# ghost.net
KiCad netlist of a schematic drawn in EAGLE
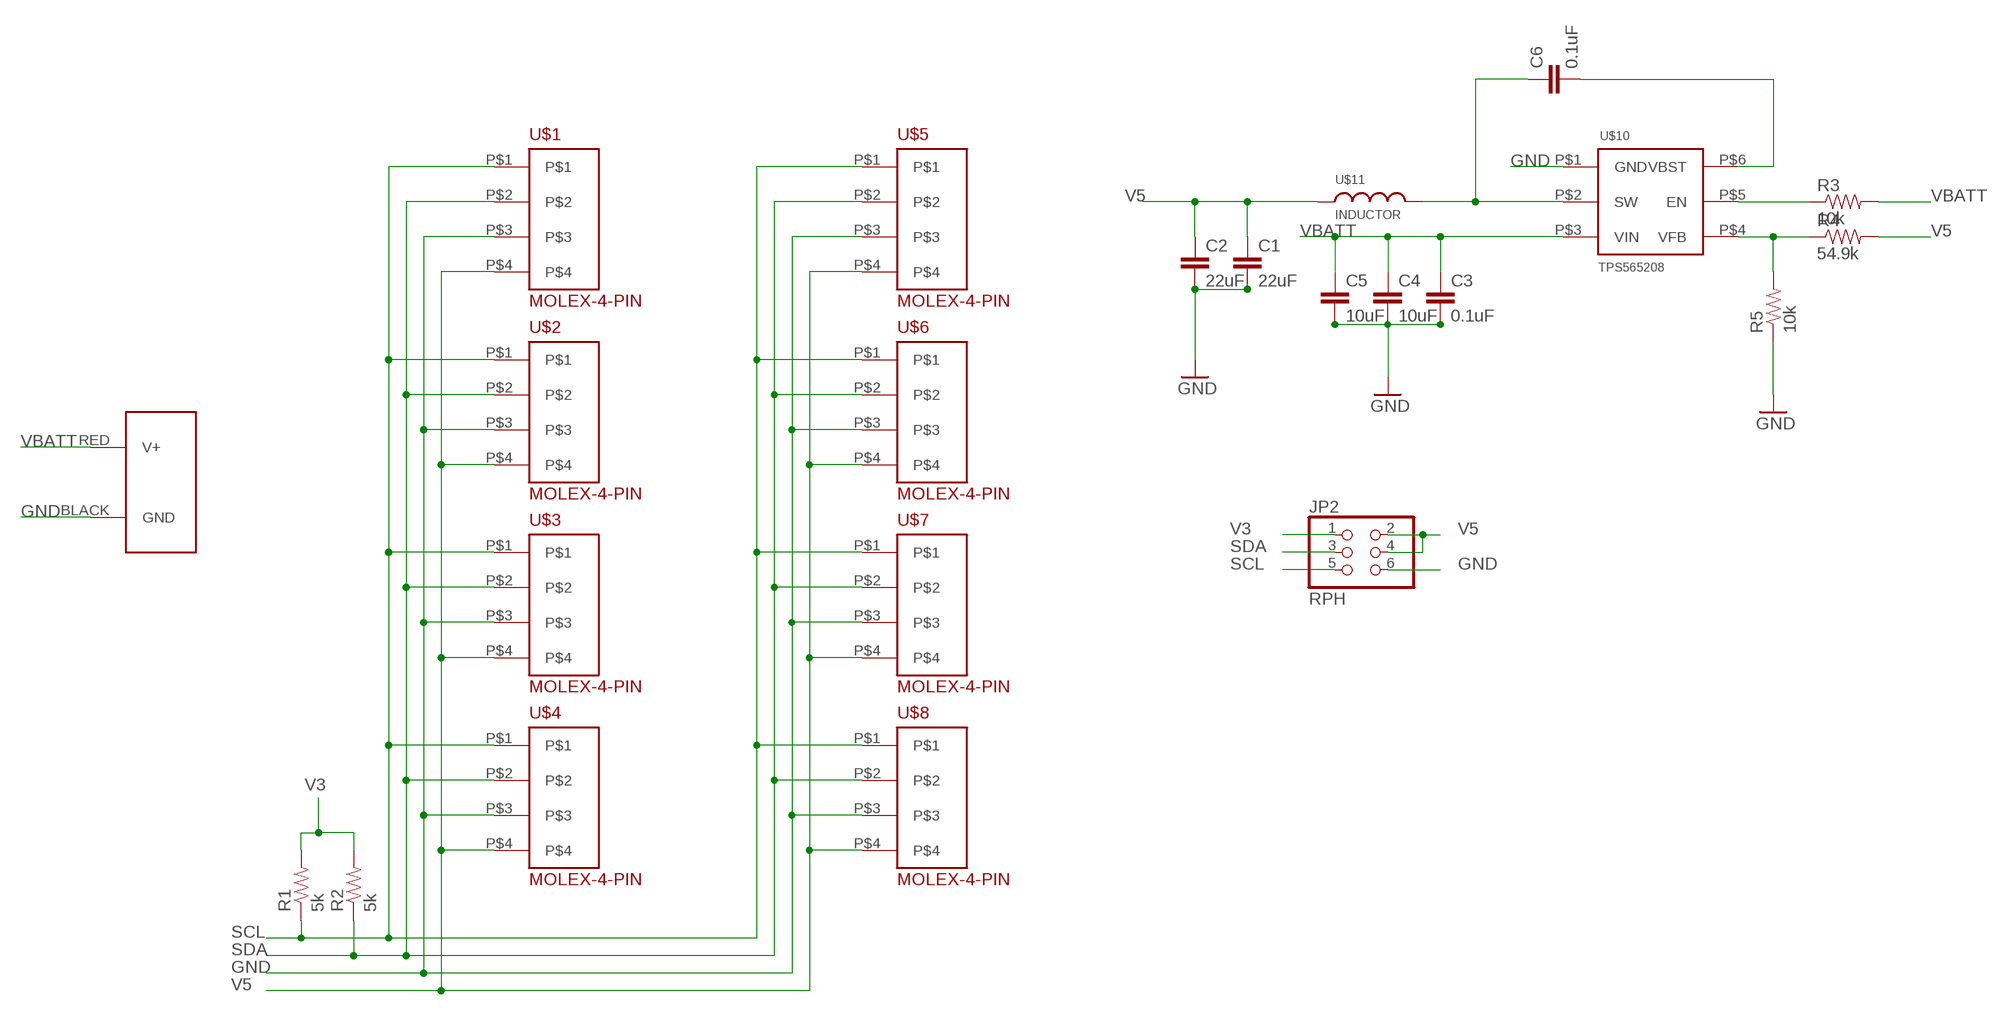
[diagram p0: schematic, sheet 1]

(export (version "E")
  (design (tool "Eeschema 10.0.6"))
  (components
    (comp (ref "C1")
      (value "22uF")
      (footprint "eagle-import:0805")
      (libsource (lib "eagle-import") (part "CAP0805"))
    )
    (comp (ref "C2")
      (value "22uF")
      (footprint "eagle-import:0805")
      (libsource (lib "eagle-import") (part "CAP0805"))
    )
    (comp (ref "C3")
      (value "0.1uF")
      (footprint "eagle-import:0805")
      (libsource (lib "eagle-import") (part "CAP0805"))
    )
    (comp (ref "C4")
      (value "10uF")
      (footprint "eagle-import:0805")
      (libsource (lib "eagle-import") (part "CAP0805"))
    )
    (comp (ref "C5")
      (value "10uF")
      (footprint "eagle-import:0805")
      (libsource (lib "eagle-import") (part "CAP0805"))
    )
    (comp (ref "C6")
      (value "0.1uF")
      (footprint "eagle-import:0805")
      (libsource (lib "eagle-import") (part "CAP0805"))
    )
    (comp (ref "J1")
      (value "POWERPOLE_POWER45A_HORIZONTAL_DRILL")
      (footprint "eagle-import:POWERPOLE_PAIR_45A_HORIZ_HOLE")
      (libsource (lib "eagle-import") (part "POWERPOLE_POWER45A_HORIZONTAL_DRILL"))
    )
    (comp (ref "JP2")
      (value "RPH")
      (footprint "eagle-import:2X03")
      (libsource (lib "eagle-import") (part "PINHD-2X3/OCT"))
    )
    (comp (ref "R1")
      (value "5k")
      (footprint "eagle-import:0805")
      (libsource (lib "eagle-import") (part "RESISTOR"))
    )
    (comp (ref "R2")
      (value "5k")
      (footprint "eagle-import:0805")
      (libsource (lib "eagle-import") (part "RESISTOR"))
    )
    (comp (ref "R3")
      (value "10k")
      (footprint "eagle-import:0805")
      (libsource (lib "eagle-import") (part "RESISTOR"))
    )
    (comp (ref "R4")
      (value "54.9k")
      (footprint "eagle-import:0805")
      (libsource (lib "eagle-import") (part "RESISTOR"))
    )
    (comp (ref "R5")
      (value "10k")
      (footprint "eagle-import:0805")
      (libsource (lib "eagle-import") (part "RESISTOR"))
    )
    (comp (ref "U$1")
      (value "MOLEX-4-PIN")
      (footprint "eagle-import:MOLEX-4-PIN")
      (libsource (lib "eagle-import") (part "MOLEX-4-PIN"))
    )
    (comp (ref "U$2")
      (value "MOLEX-4-PIN")
      (footprint "eagle-import:MOLEX-4-PIN")
      (libsource (lib "eagle-import") (part "MOLEX-4-PIN"))
    )
    (comp (ref "U$3")
      (value "MOLEX-4-PIN")
      (footprint "eagle-import:MOLEX-4-PIN")
      (libsource (lib "eagle-import") (part "MOLEX-4-PIN"))
    )
    (comp (ref "U$4")
      (value "MOLEX-4-PIN")
      (footprint "eagle-import:MOLEX-4-PIN")
      (libsource (lib "eagle-import") (part "MOLEX-4-PIN"))
    )
    (comp (ref "U$5")
      (value "MOLEX-4-PIN")
      (footprint "eagle-import:MOLEX-4-PIN")
      (libsource (lib "eagle-import") (part "MOLEX-4-PIN"))
    )
    (comp (ref "U$6")
      (value "MOLEX-4-PIN")
      (footprint "eagle-import:MOLEX-4-PIN")
      (libsource (lib "eagle-import") (part "MOLEX-4-PIN"))
    )
    (comp (ref "U$7")
      (value "MOLEX-4-PIN")
      (footprint "eagle-import:MOLEX-4-PIN")
      (libsource (lib "eagle-import") (part "MOLEX-4-PIN"))
    )
    (comp (ref "U$8")
      (value "MOLEX-4-PIN")
      (footprint "eagle-import:MOLEX-4-PIN")
      (libsource (lib "eagle-import") (part "MOLEX-4-PIN"))
    )
    (comp (ref "U$10")
      (value "TPS565208")
      (footprint "eagle-import:SOT-23-THIN-6")
      (libsource (lib "eagle-import") (part "TPS565208"))
    )
    (comp (ref "U$11")
      (value "INDUCTOR")
      (footprint "eagle-import:0805")
      (libsource (lib "eagle-import") (part "INDUCTOR"))
    )
  )
  (nets
    (net (code "1") (name "/SCL") (class "Default")
      (node (ref "JP2") (pin "5") (pinfunction "5_5") (pintype "passive"))
      (node (ref "R1") (pin "1") (pinfunction "1_1") (pintype "passive"))
      (node (ref "U$1") (pin "P$1") (pinfunction "P$1_P$1") (pintype "bidirectional"))
      (node (ref "U$2") (pin "P$1") (pinfunction "P$1_P$1") (pintype "bidirectional"))
      (node (ref "U$3") (pin "P$1") (pinfunction "P$1_P$1") (pintype "bidirectional"))
      (node (ref "U$4") (pin "P$1") (pinfunction "P$1_P$1") (pintype "bidirectional"))
      (node (ref "U$5") (pin "P$1") (pinfunction "P$1_P$1") (pintype "bidirectional"))
      (node (ref "U$6") (pin "P$1") (pinfunction "P$1_P$1") (pintype "bidirectional"))
      (node (ref "U$7") (pin "P$1") (pinfunction "P$1_P$1") (pintype "bidirectional"))
      (node (ref "U$8") (pin "P$1") (pinfunction "P$1_P$1") (pintype "bidirectional"))
    )
    (net (code "2") (name "/SDA") (class "Default")
      (node (ref "JP2") (pin "3") (pinfunction "3_3") (pintype "passive"))
      (node (ref "R2") (pin "1") (pinfunction "1_1") (pintype "passive"))
      (node (ref "U$1") (pin "P$2") (pinfunction "P$2_P$2") (pintype "bidirectional"))
      (node (ref "U$2") (pin "P$2") (pinfunction "P$2_P$2") (pintype "bidirectional"))
      (node (ref "U$3") (pin "P$2") (pinfunction "P$2_P$2") (pintype "bidirectional"))
      (node (ref "U$4") (pin "P$2") (pinfunction "P$2_P$2") (pintype "bidirectional"))
      (node (ref "U$5") (pin "P$2") (pinfunction "P$2_P$2") (pintype "bidirectional"))
      (node (ref "U$6") (pin "P$2") (pinfunction "P$2_P$2") (pintype "bidirectional"))
      (node (ref "U$7") (pin "P$2") (pinfunction "P$2_P$2") (pintype "bidirectional"))
      (node (ref "U$8") (pin "P$2") (pinfunction "P$2_P$2") (pintype "bidirectional"))
    )
    (net (code "3") (name "/V3") (class "Default")
      (node (ref "JP2") (pin "1") (pinfunction "1_1") (pintype "passive"))
      (node (ref "R1") (pin "2") (pinfunction "2_2") (pintype "passive"))
      (node (ref "R2") (pin "2") (pinfunction "2_2") (pintype "passive"))
    )
    (net (code "4") (name "/V5") (class "Default")
      (node (ref "C1") (pin "1") (pinfunction "1_1") (pintype "passive"))
      (node (ref "C2") (pin "1") (pinfunction "1_1") (pintype "passive"))
      (node (ref "JP2") (pin "2") (pinfunction "2_2") (pintype "passive"))
      (node (ref "JP2") (pin "4") (pinfunction "4_4") (pintype "passive"))
      (node (ref "R4") (pin "2") (pinfunction "2_2") (pintype "passive"))
      (node (ref "U$1") (pin "P$4") (pinfunction "P$4_P$4") (pintype "bidirectional"))
      (node (ref "U$11") (pin "P$1") (pinfunction "1_P$1") (pintype "passive"))
      (node (ref "U$2") (pin "P$4") (pinfunction "P$4_P$4") (pintype "bidirectional"))
      (node (ref "U$3") (pin "P$4") (pinfunction "P$4_P$4") (pintype "bidirectional"))
      (node (ref "U$4") (pin "P$4") (pinfunction "P$4_P$4") (pintype "bidirectional"))
      (node (ref "U$5") (pin "P$4") (pinfunction "P$4_P$4") (pintype "bidirectional"))
      (node (ref "U$6") (pin "P$4") (pinfunction "P$4_P$4") (pintype "bidirectional"))
      (node (ref "U$7") (pin "P$4") (pinfunction "P$4_P$4") (pintype "bidirectional"))
      (node (ref "U$8") (pin "P$4") (pinfunction "P$4_P$4") (pintype "bidirectional"))
    )
    (net (code "5") (name "/VBATT") (class "Default")
      (node (ref "C3") (pin "1") (pinfunction "1_1") (pintype "passive"))
      (node (ref "C4") (pin "1") (pinfunction "1_1") (pintype "passive"))
      (node (ref "C5") (pin "1") (pinfunction "1_1") (pintype "passive"))
      (node (ref "J1") (pin "RED") (pinfunction "V+_RED") (pintype "power_in"))
      (node (ref "R3") (pin "2") (pinfunction "2_2") (pintype "passive"))
      (node (ref "U$10") (pin "P$3") (pinfunction "VIN_P$3") (pintype "bidirectional"))
    )
    (net (code "6") (name "GND") (class "Default")
      (node (ref "C1") (pin "2") (pinfunction "2_2") (pintype "passive"))
      (node (ref "C2") (pin "2") (pinfunction "2_2") (pintype "passive"))
      (node (ref "C3") (pin "2") (pinfunction "2_2") (pintype "passive"))
      (node (ref "C4") (pin "2") (pinfunction "2_2") (pintype "passive"))
      (node (ref "C5") (pin "2") (pinfunction "2_2") (pintype "passive"))
      (node (ref "J1") (pin "BLACK") (pinfunction "GND_BLACK") (pintype "power_in"))
      (node (ref "JP2") (pin "6") (pinfunction "6_6") (pintype "passive"))
      (node (ref "R5") (pin "1") (pinfunction "1_1") (pintype "passive"))
      (node (ref "U$1") (pin "P$3") (pinfunction "P$3_P$3") (pintype "bidirectional"))
      (node (ref "U$10") (pin "P$1") (pinfunction "GND_P$1") (pintype "bidirectional"))
      (node (ref "U$2") (pin "P$3") (pinfunction "P$3_P$3") (pintype "bidirectional"))
      (node (ref "U$3") (pin "P$3") (pinfunction "P$3_P$3") (pintype "bidirectional"))
      (node (ref "U$4") (pin "P$3") (pinfunction "P$3_P$3") (pintype "bidirectional"))
      (node (ref "U$5") (pin "P$3") (pinfunction "P$3_P$3") (pintype "bidirectional"))
      (node (ref "U$6") (pin "P$3") (pinfunction "P$3_P$3") (pintype "bidirectional"))
      (node (ref "U$7") (pin "P$3") (pinfunction "P$3_P$3") (pintype "bidirectional"))
      (node (ref "U$8") (pin "P$3") (pinfunction "P$3_P$3") (pintype "bidirectional"))
    )
    (net (code "7") (name "Net-(U$10-EN)") (class "Default")
      (node (ref "R3") (pin "1") (pinfunction "1_1") (pintype "passive"))
      (node (ref "U$10") (pin "P$5") (pinfunction "EN_P$5") (pintype "bidirectional"))
    )
    (net (code "8") (name "Net-(U$10-SW)") (class "Default")
      (node (ref "C6") (pin "1") (pinfunction "1_1") (pintype "passive"))
      (node (ref "U$10") (pin "P$2") (pinfunction "SW_P$2") (pintype "bidirectional"))
      (node (ref "U$11") (pin "P$2") (pinfunction "2_P$2") (pintype "passive"))
    )
    (net (code "9") (name "Net-(U$10-VBST)") (class "Default")
      (node (ref "C6") (pin "2") (pinfunction "2_2") (pintype "passive"))
      (node (ref "U$10") (pin "P$6") (pinfunction "VBST_P$6") (pintype "bidirectional"))
    )
    (net (code "10") (name "Net-(U$10-VFB)") (class "Default")
      (node (ref "R4") (pin "1") (pinfunction "1_1") (pintype "passive"))
      (node (ref "R5") (pin "2") (pinfunction "2_2") (pintype "passive"))
      (node (ref "U$10") (pin "P$4") (pinfunction "VFB_P$4") (pintype "bidirectional"))
    )
  )
)
